# automaton.net
KiCad netlist of a schematic drawn in EAGLE
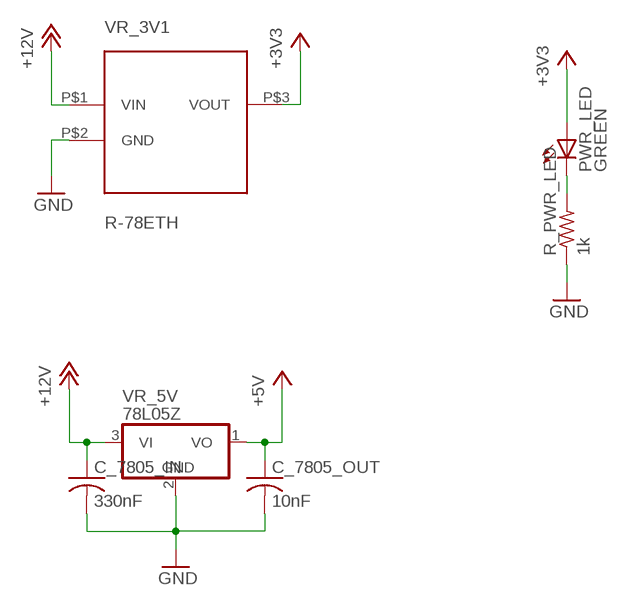
[diagram p0: schematic, sheet 1]
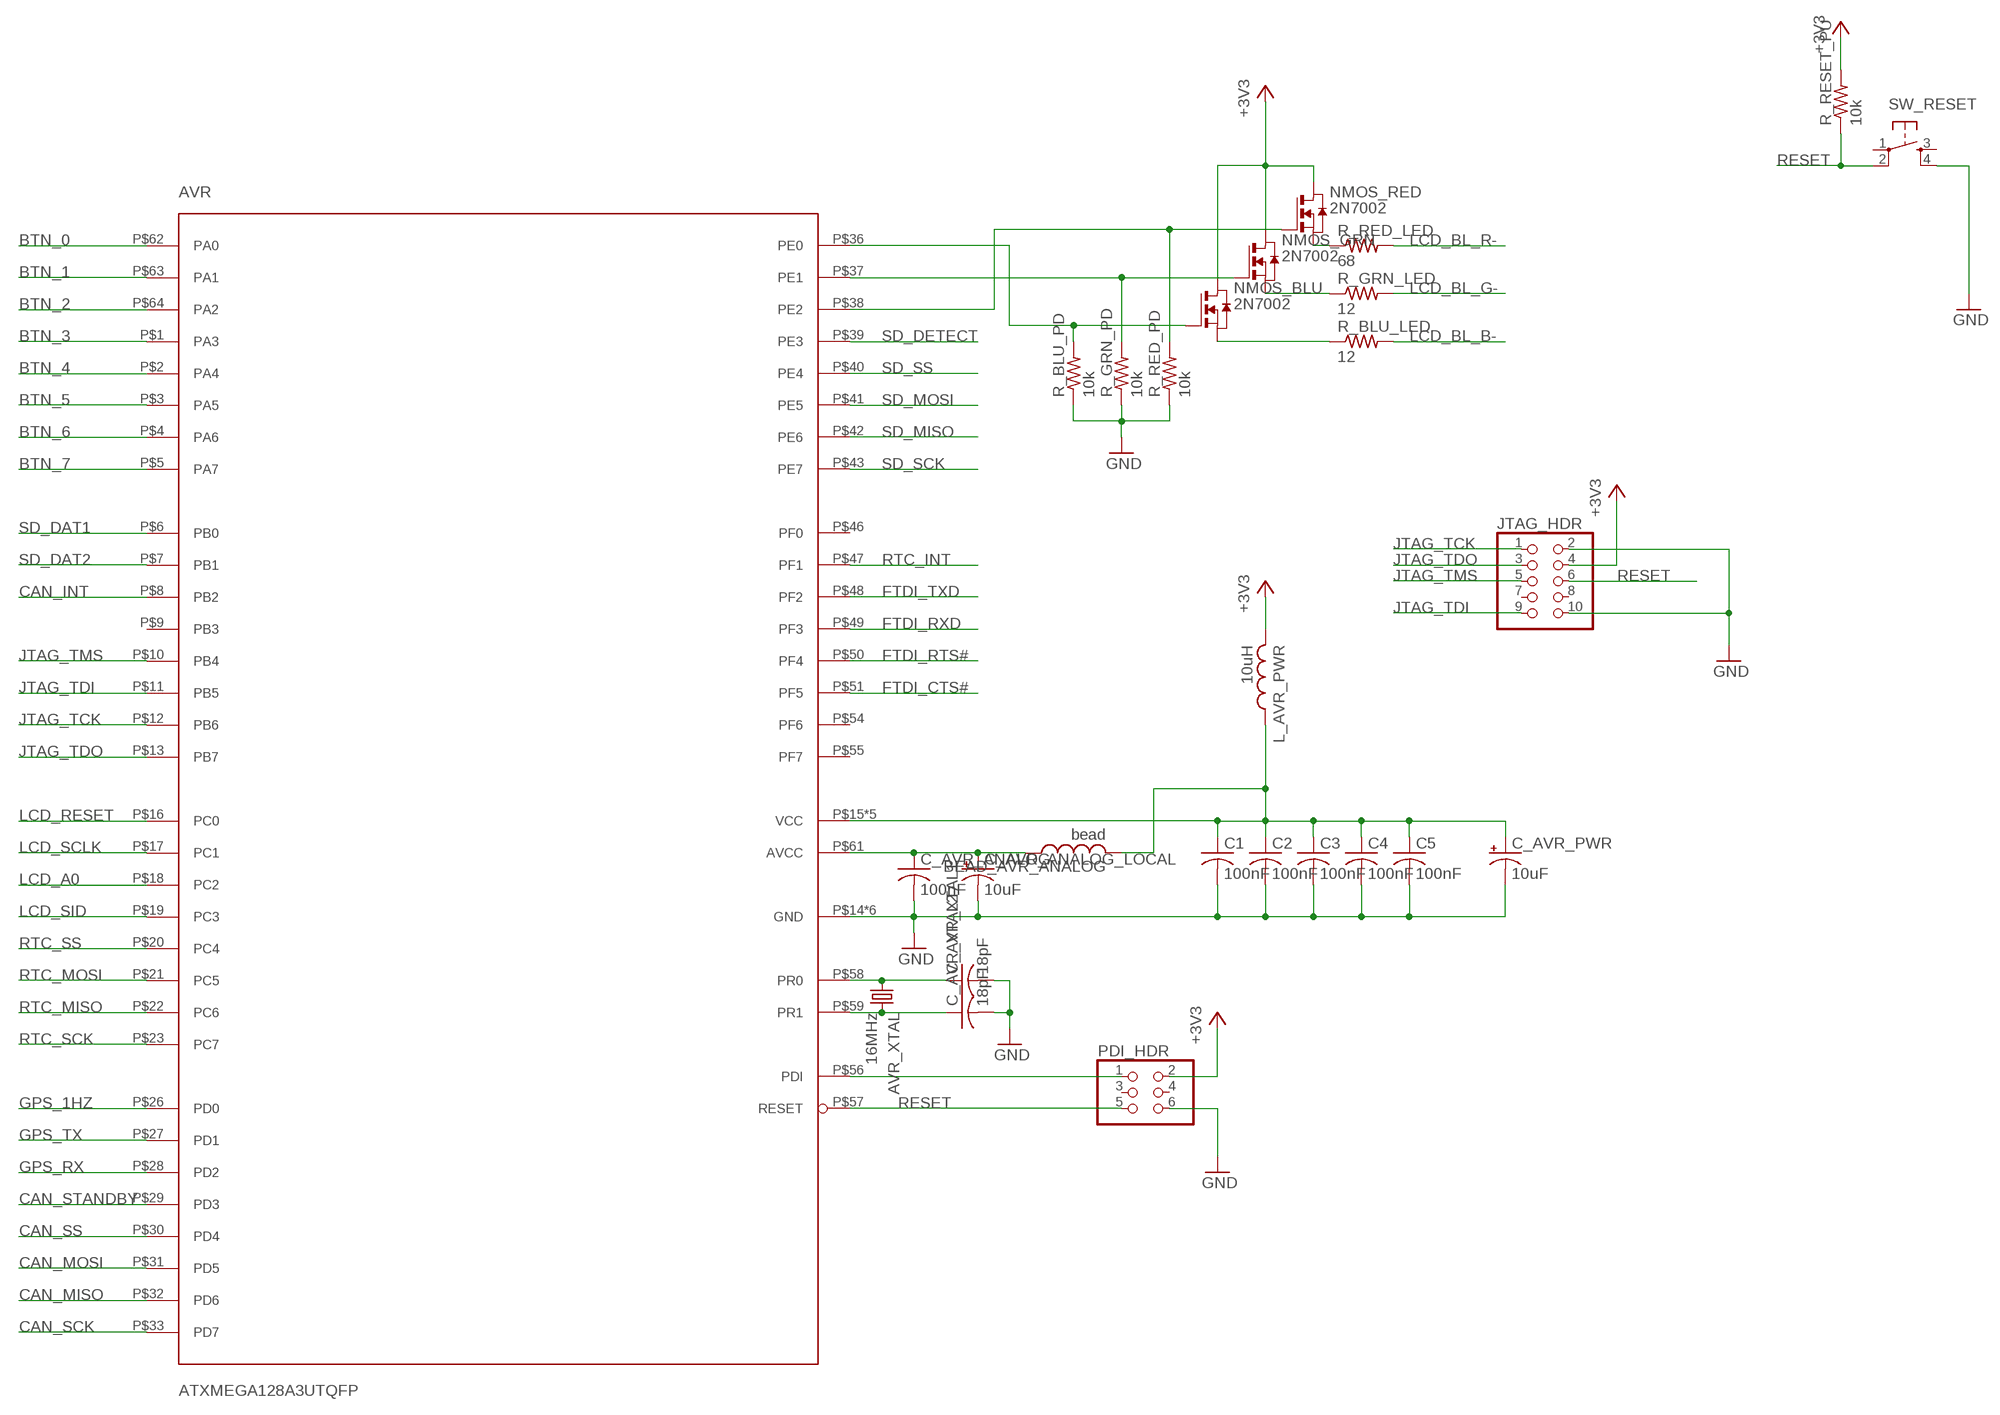
[diagram p1: schematic, sheet 2]
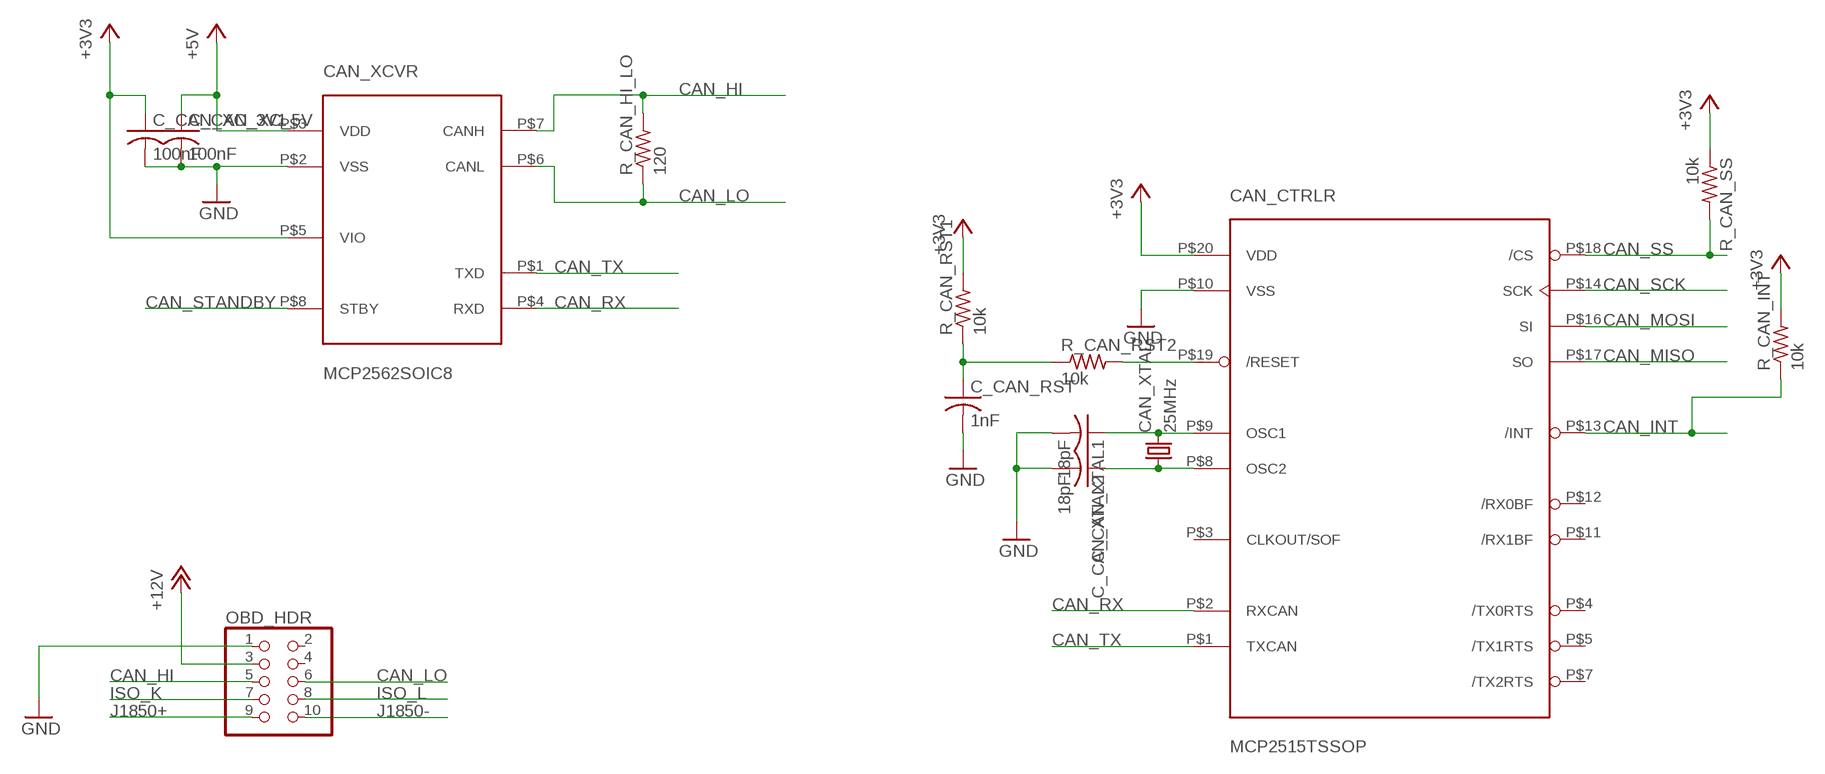
[diagram p2: schematic, sheet 3]
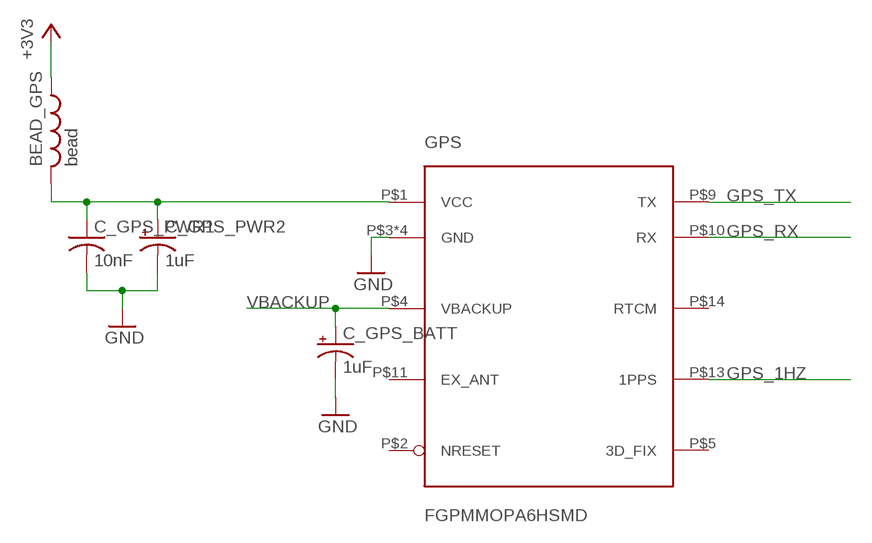
[diagram p3: schematic, sheet 4]
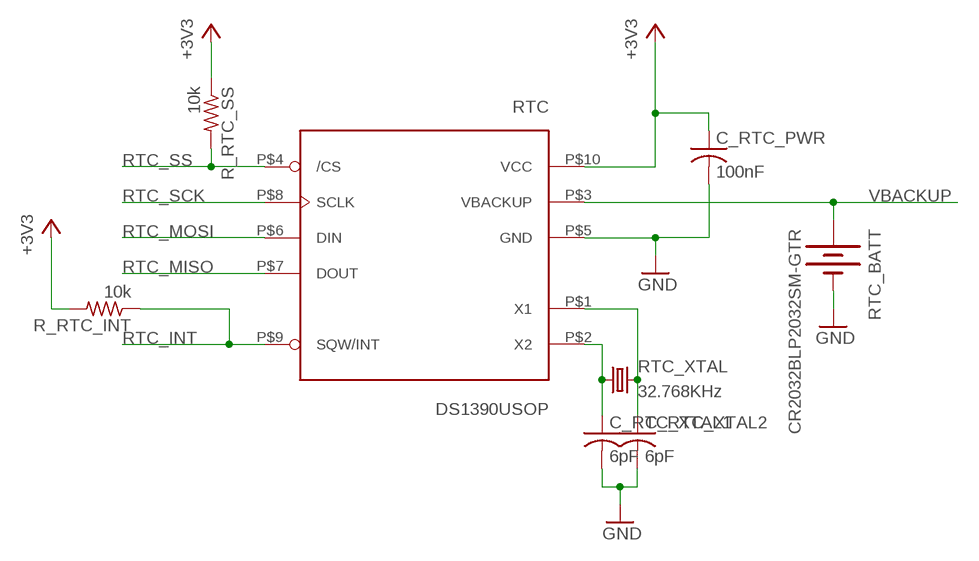
[diagram p4: schematic, sheet 5]
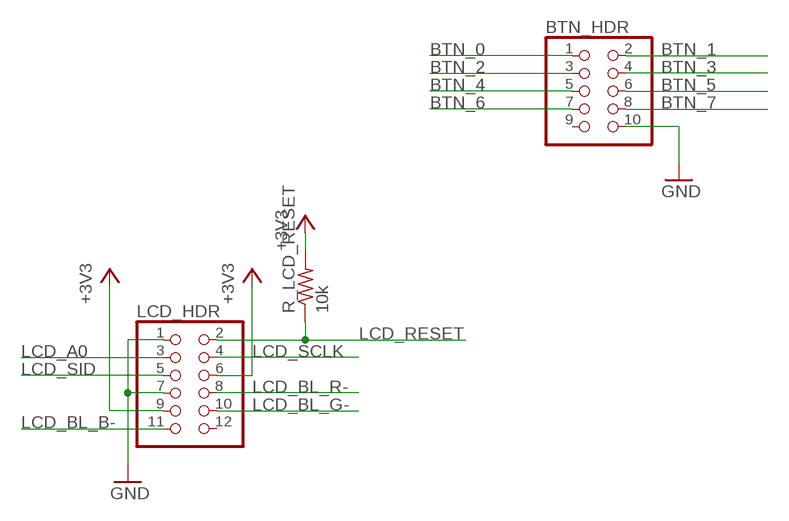
[diagram p5: schematic, sheet 6]
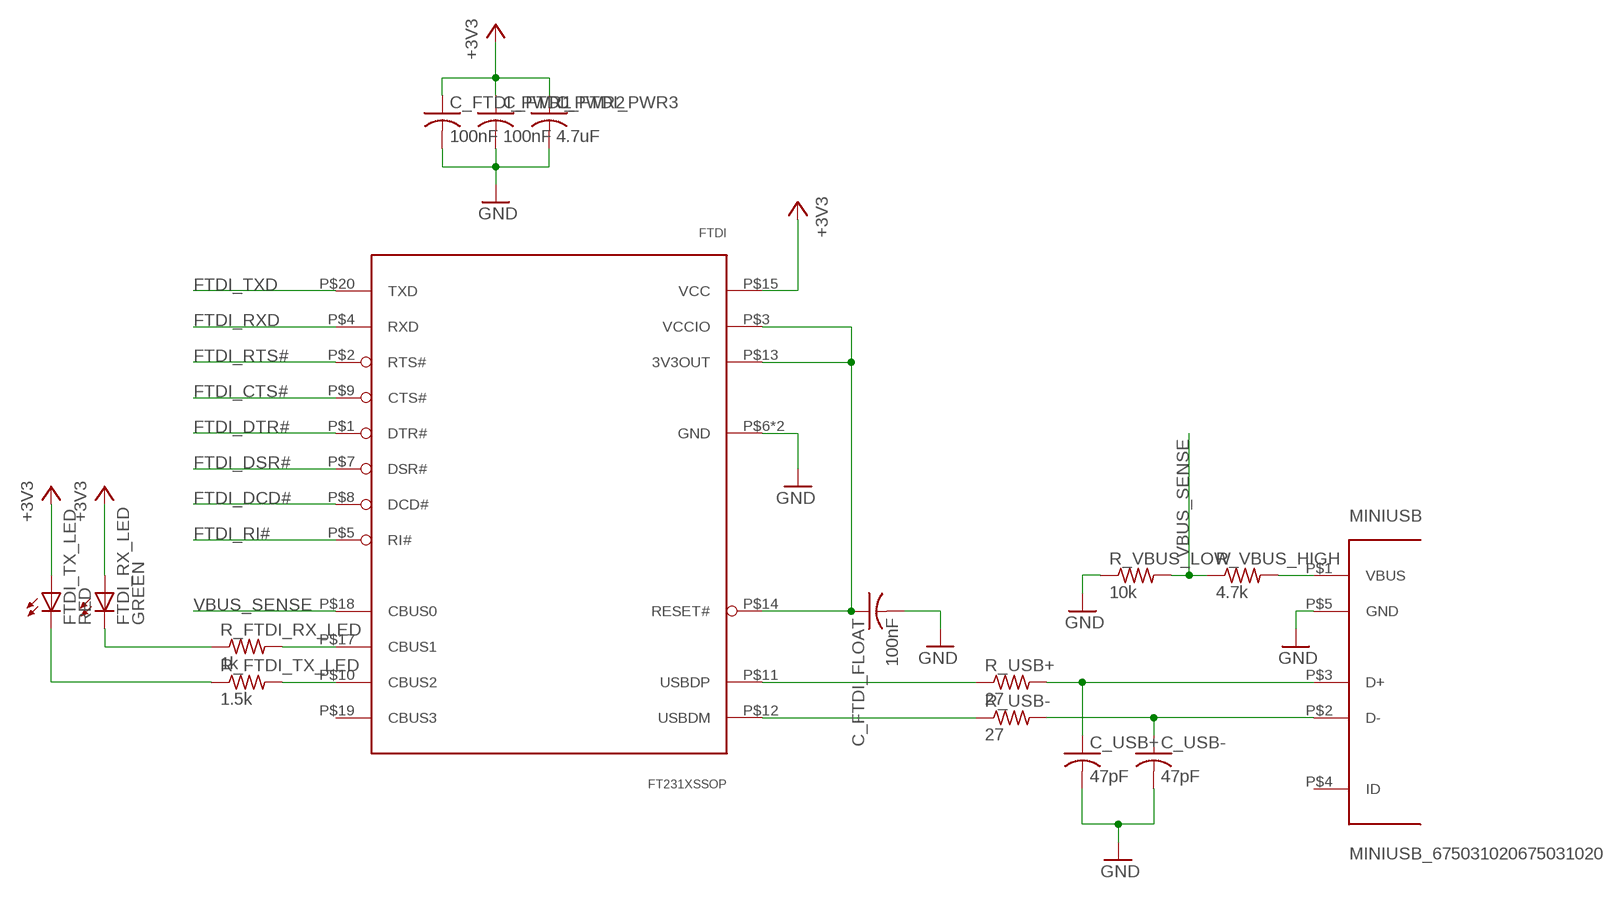
[diagram p6: schematic, sheet 7]
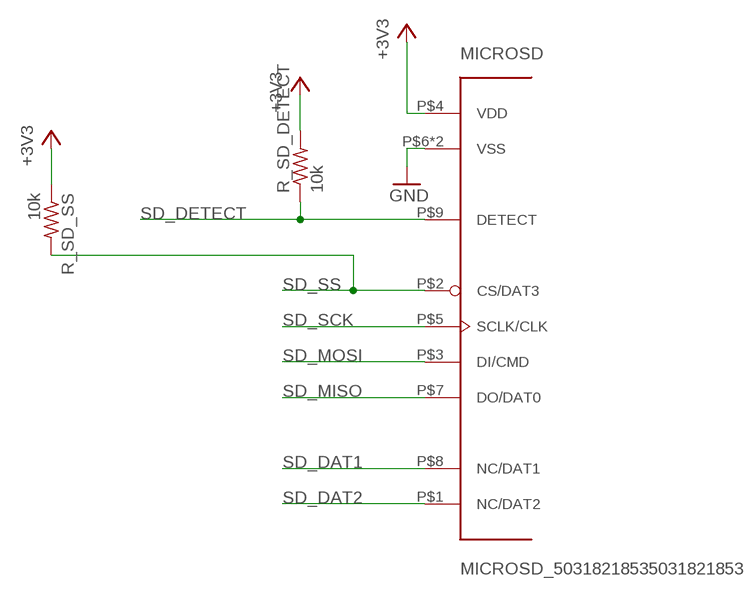
[diagram p7: schematic, sheet 8]

(export (version "E")
  (design (tool "Eeschema 10.0.6"))
  (components
    (comp (ref "C_RTC_PWR")
      (value "100nF")
      (footprint "eagle-import:C1206")
      (libsource (lib "eagle-import") (part "C-USC1206"))
    )
    (comp (ref "C_RTC_XTAL1")
      (value "6pF")
      (footprint "eagle-import:C1206")
      (libsource (lib "eagle-import") (part "C-USC1206"))
    )
    (comp (ref "C_RTC_XTAL2")
      (value "6pF")
      (footprint "eagle-import:C1206")
      (libsource (lib "eagle-import") (part "C-USC1206"))
    )
    (comp (ref "RTC")
      (value "DS1390USOP")
      (footprint "eagle-import:MAXIM_10USOP")
      (libsource (lib "eagle-import") (part "DS1390USOP"))
    )
    (comp (ref "RTC_BATT")
      (value "CR2032BLP2032SM-GTR")
      (footprint "eagle-import:BLP2032SM-GTR")
      (libsource (lib "eagle-import") (part "CR2032BLP2032SM-GTR"))
    )
    (comp (ref "RTC_XTAL")
      (value "32.768KHz")
      (footprint "eagle-import:TC26V")
      (libsource (lib "eagle-import") (part "CRYSTALTC26V"))
    )
    (comp (ref "R_RTC_INT")
      (value "10k")
      (footprint "eagle-import:R1206")
      (libsource (lib "eagle-import") (part "R-US_R1206"))
    )
    (comp (ref "R_RTC_SS")
      (value "10k")
      (footprint "eagle-import:R1206")
      (libsource (lib "eagle-import") (part "R-US_R1206"))
    )
    (comp (ref "BTN_HDR")
      (value "PINHD-2X05_2.54")
      (footprint "eagle-import:2X05")
      (libsource (lib "eagle-import") (part "PINHD-2X05_2.54"))
    )
    (comp (ref "LCD_HDR")
      (value "PINHD-2X06_2.54")
      (footprint "eagle-import:2X06")
      (libsource (lib "eagle-import") (part "PINHD-2X06_2.54"))
    )
    (comp (ref "R_LCD_RESET")
      (value "10k")
      (footprint "eagle-import:R1206")
      (libsource (lib "eagle-import") (part "R-US_R1206"))
    )
    (comp (ref "C_FTDI_FLOAT")
      (value "100nF")
      (footprint "eagle-import:C1206")
      (libsource (lib "eagle-import") (part "C-USC1206"))
    )
    (comp (ref "C_FTDI_PWR1")
      (value "100nF")
      (footprint "eagle-import:C1206")
      (libsource (lib "eagle-import") (part "C-USC1206"))
    )
    (comp (ref "C_FTDI_PWR2")
      (value "100nF")
      (footprint "eagle-import:C1206")
      (libsource (lib "eagle-import") (part "C-USC1206"))
    )
    (comp (ref "C_FTDI_PWR3")
      (value "4.7uF")
      (footprint "eagle-import:C1206")
      (libsource (lib "eagle-import") (part "C-USC1206"))
    )
    (comp (ref "C_USB+")
      (value "47pF")
      (footprint "eagle-import:C1206")
      (libsource (lib "eagle-import") (part "C-USC1206"))
    )
    (comp (ref "C_USB-")
      (value "47pF")
      (footprint "eagle-import:C1206")
      (libsource (lib "eagle-import") (part "C-USC1206"))
    )
    (comp (ref "FTDI")
      (value "FT231XSSOP")
      (footprint "eagle-import:FTDI_SSOP20")
      (libsource (lib "eagle-import") (part "FT231XSSOP"))
    )
    (comp (ref "FTDI_RX_LED")
      (value "GREEN")
      (footprint "eagle-import:CHIPLED_1206")
      (libsource (lib "eagle-import") (part "LEDCHIPLED_1206"))
    )
    (comp (ref "FTDI_TX_LED")
      (value "RED")
      (footprint "eagle-import:CHIPLED_1206")
      (libsource (lib "eagle-import") (part "LEDCHIPLED_1206"))
    )
    (comp (ref "MINIUSB")
      (value "MINIUSB_675031020675031020")
      (footprint "eagle-import:MINIUSB_675031020")
      (libsource (lib "eagle-import") (part "MINIUSB_675031020675031020"))
    )
    (comp (ref "R_FTDI_RX_LED")
      (value "1k")
      (footprint "eagle-import:R1206")
      (libsource (lib "eagle-import") (part "R-US_R1206"))
    )
    (comp (ref "R_FTDI_TX_LED")
      (value "1.5k")
      (footprint "eagle-import:R1206")
      (libsource (lib "eagle-import") (part "R-US_R1206"))
    )
    (comp (ref "R_USB+")
      (value "27")
      (footprint "eagle-import:R1206")
      (libsource (lib "eagle-import") (part "R-US_R1206"))
    )
    (comp (ref "R_USB-")
      (value "27")
      (footprint "eagle-import:R1206")
      (libsource (lib "eagle-import") (part "R-US_R1206"))
    )
    (comp (ref "R_VBUS_HIGH")
      (value "4.7k")
      (footprint "eagle-import:R1206")
      (libsource (lib "eagle-import") (part "R-US_R1206"))
    )
    (comp (ref "R_VBUS_LOW")
      (value "10k")
      (footprint "eagle-import:R1206")
      (libsource (lib "eagle-import") (part "R-US_R1206"))
    )
    (comp (ref "C_7805_IN")
      (value "330nF")
      (footprint "eagle-import:C1206")
      (libsource (lib "eagle-import") (part "C-USC1206"))
    )
    (comp (ref "C_7805_OUT")
      (value "10nF")
      (footprint "eagle-import:C1206")
      (libsource (lib "eagle-import") (part "C-USC1206"))
    )
    (comp (ref "PWR_LED")
      (value "GREEN")
      (footprint "eagle-import:CHIPLED_1206")
      (libsource (lib "eagle-import") (part "LEDCHIPLED_1206"))
    )
    (comp (ref "R_PWR_LED")
      (value "1k")
      (footprint "eagle-import:R1206")
      (libsource (lib "eagle-import") (part "R-US_R1206"))
    )
    (comp (ref "VR_3V1")
      (value "R-78ETH")
      (footprint "eagle-import:R-78E")
      (libsource (lib "eagle-import") (part "R-78ETH"))
    )
    (comp (ref "VR_5V")
      (value "78L05Z")
      (footprint "eagle-import:TO92")
      (libsource (lib "eagle-import") (part "78ZL05"))
    )
    (comp (ref "MICROSD")
      (value "MICROSD_50318218535031821853")
      (footprint "eagle-import:MICROSD_5031821853")
      (libsource (lib "eagle-import") (part "MICROSD_50318218535031821853"))
    )
    (comp (ref "R_SD_DETECT")
      (value "10k")
      (footprint "eagle-import:R1206")
      (libsource (lib "eagle-import") (part "R-US_R1206"))
    )
    (comp (ref "R_SD_SS")
      (value "10k")
      (footprint "eagle-import:R1206")
      (libsource (lib "eagle-import") (part "R-US_R1206"))
    )
    (comp (ref "CAN_CTRLR")
      (value "MCP2515TSSOP")
      (footprint "eagle-import:MICROCHIP_TSSOP20")
      (libsource (lib "eagle-import") (part "MCP2515TSSOP"))
    )
    (comp (ref "CAN_XCVR")
      (value "MCP2562SOIC8")
      (footprint "eagle-import:MICROCHIP_SOIC8")
      (libsource (lib "eagle-import") (part "MCP2562SOIC8"))
    )
    (comp (ref "CAN_XTAL")
      (value "25MHz")
      (footprint "eagle-import:HC49_S")
      (libsource (lib "eagle-import") (part "CRYSTALHC49S"))
    )
    (comp (ref "C_CAN_RST")
      (value "1nF")
      (footprint "eagle-import:C1206")
      (libsource (lib "eagle-import") (part "C-USC1206"))
    )
    (comp (ref "C_CAN_XC_3V1")
      (value "100nF")
      (footprint "eagle-import:C1206")
      (libsource (lib "eagle-import") (part "C-USC1206"))
    )
    (comp (ref "C_CAN_XC_5V")
      (value "100nF")
      (footprint "eagle-import:C1206")
      (libsource (lib "eagle-import") (part "C-USC1206"))
    )
    (comp (ref "C_CAN_XTAL1")
      (value "18pF")
      (footprint "eagle-import:C1206")
      (libsource (lib "eagle-import") (part "C-USC1206"))
    )
    (comp (ref "C_CAN_XTAL2")
      (value "18pF")
      (footprint "eagle-import:C1206")
      (libsource (lib "eagle-import") (part "C-USC1206"))
    )
    (comp (ref "OBD_HDR")
      (value "PINHD-2X05_2.54-90°")
      (footprint "eagle-import:2X05_90")
      (libsource (lib "eagle-import") (part "PINHD-2X05_2.54-90°"))
    )
    (comp (ref "R_CAN_HI_LO")
      (value "120")
      (footprint "eagle-import:R1206")
      (libsource (lib "eagle-import") (part "R-US_R1206"))
    )
    (comp (ref "R_CAN_INT")
      (value "10k")
      (footprint "eagle-import:R1206")
      (libsource (lib "eagle-import") (part "R-US_R1206"))
    )
    (comp (ref "R_CAN_RST1")
      (value "10k")
      (footprint "eagle-import:R1206")
      (libsource (lib "eagle-import") (part "R-US_R1206"))
    )
    (comp (ref "R_CAN_RST2")
      (value "10k")
      (footprint "eagle-import:R1206")
      (libsource (lib "eagle-import") (part "R-US_R1206"))
    )
    (comp (ref "R_CAN_SS")
      (value "10k")
      (footprint "eagle-import:R1206")
      (libsource (lib "eagle-import") (part "R-US_R1206"))
    )
    (comp (ref "AVR")
      (value "ATXMEGA128A3UTQFP")
      (footprint "eagle-import:ATMEL_TQFP64")
      (libsource (lib "eagle-import") (part "ATXMEGA128A3UTQFP"))
    )
    (comp (ref "AVR_XTAL")
      (value "16MHz")
      (footprint "eagle-import:HC49_S")
      (libsource (lib "eagle-import") (part "CRYSTALHC49S"))
    )
    (comp (ref "BEAD_AVR_ANALOG")
      (value "bead")
      (footprint "eagle-import:L1812")
      (libsource (lib "eagle-import") (part "L-USL1812"))
    )
    (comp (ref "C1")
      (value "100nF")
      (footprint "eagle-import:C1206")
      (libsource (lib "eagle-import") (part "C-USC1206"))
    )
    (comp (ref "C2")
      (value "100nF")
      (footprint "eagle-import:C1206")
      (libsource (lib "eagle-import") (part "C-USC1206"))
    )
    (comp (ref "C3")
      (value "100nF")
      (footprint "eagle-import:C1206")
      (libsource (lib "eagle-import") (part "C-USC1206"))
    )
    (comp (ref "C4")
      (value "100nF")
      (footprint "eagle-import:C1206")
      (libsource (lib "eagle-import") (part "C-USC1206"))
    )
    (comp (ref "C5")
      (value "100nF")
      (footprint "eagle-import:C1206")
      (libsource (lib "eagle-import") (part "C-USC1206"))
    )
    (comp (ref "C_AVR_ANALOG")
      (value "100nF")
      (footprint "eagle-import:C1206")
      (libsource (lib "eagle-import") (part "C-USC1206"))
    )
    (comp (ref "C_AVR_ANALOG_LOCAL")
      (value "10uF")
      (footprint "eagle-import:E2-5")
      (libsource (lib "eagle-import") (part "CPOL-USE2-5"))
    )
    (comp (ref "C_AVR_PWR")
      (value "10uF")
      (footprint "eagle-import:E2-5")
      (libsource (lib "eagle-import") (part "CPOL-USE2-5"))
    )
    (comp (ref "C_AVR_XTAL1")
      (value "18pF")
      (footprint "eagle-import:C1206")
      (libsource (lib "eagle-import") (part "C-USC1206"))
    )
    (comp (ref "C_AVR_XTAL2")
      (value "18pF")
      (footprint "eagle-import:C1206")
      (libsource (lib "eagle-import") (part "C-USC1206"))
    )
    (comp (ref "JTAG_HDR")
      (value "PINHD-2X05_2.54")
      (footprint "eagle-import:2X05")
      (libsource (lib "eagle-import") (part "PINHD-2X05_2.54"))
    )
    (comp (ref "L_AVR_PWR")
      (value "10uH")
      (footprint "eagle-import:L1812")
      (libsource (lib "eagle-import") (part "L-USL1812"))
    )
    (comp (ref "NMOS_BLU")
      (value "2N7002")
      (footprint "eagle-import:SOT-23")
      (libsource (lib "eagle-import") (part "NMOSSOT23"))
    )
    (comp (ref "NMOS_GRN")
      (value "2N7002")
      (footprint "eagle-import:SOT-23")
      (libsource (lib "eagle-import") (part "NMOSSOT23"))
    )
    (comp (ref "NMOS_RED")
      (value "2N7002")
      (footprint "eagle-import:SOT-23")
      (libsource (lib "eagle-import") (part "NMOSSOT23"))
    )
    (comp (ref "PDI_HDR")
      (value "PINHD-2X03_2.54")
      (footprint "eagle-import:2X03")
      (libsource (lib "eagle-import") (part "PINHD-2X03_2.54"))
    )
    (comp (ref "R_BLU_LED")
      (value "12")
      (footprint "eagle-import:R1206")
      (libsource (lib "eagle-import") (part "R-US_R1206"))
    )
    (comp (ref "R_BLU_PD")
      (value "10k")
      (footprint "eagle-import:R1206")
      (libsource (lib "eagle-import") (part "R-US_R1206"))
    )
    (comp (ref "R_GRN_LED")
      (value "12")
      (footprint "eagle-import:R1206")
      (libsource (lib "eagle-import") (part "R-US_R1206"))
    )
    (comp (ref "R_GRN_PD")
      (value "10k")
      (footprint "eagle-import:R1206")
      (libsource (lib "eagle-import") (part "R-US_R1206"))
    )
    (comp (ref "R_RED_LED")
      (value "68")
      (footprint "eagle-import:R1206")
      (libsource (lib "eagle-import") (part "R-US_R1206"))
    )
    (comp (ref "R_RED_PD")
      (value "10k")
      (footprint "eagle-import:R1206")
      (libsource (lib "eagle-import") (part "R-US_R1206"))
    )
    (comp (ref "R_RESET_PU")
      (value "10k")
      (footprint "eagle-import:R1206")
      (libsource (lib "eagle-import") (part "R-US_R1206"))
    )
    (comp (ref "SW_RESET")
      (value "TAC_SWITCHSMD")
      (footprint "eagle-import:TACTILE_SWITCH_SMD")
      (libsource (lib "eagle-import") (part "TAC_SWITCHSMD"))
    )
    (comp (ref "BEAD_GPS")
      (value "bead")
      (footprint "eagle-import:L1812")
      (libsource (lib "eagle-import") (part "L-USL1812"))
    )
    (comp (ref "C_GPS_BATT")
      (value "1uF")
      (footprint "eagle-import:E2-5")
      (libsource (lib "eagle-import") (part "CPOL-USE2-5"))
    )
    (comp (ref "C_GPS_PWR1")
      (value "10nF")
      (footprint "eagle-import:C1206")
      (libsource (lib "eagle-import") (part "C-USC1206"))
    )
    (comp (ref "C_GPS_PWR2")
      (value "1uF")
      (footprint "eagle-import:E2-5")
      (libsource (lib "eagle-import") (part "CPOL-USE2-5"))
    )
    (comp (ref "GPS")
      (value "FGPMMOPA6HSMD")
      (footprint "eagle-import:FGPMMOPA6H")
      (libsource (lib "eagle-import") (part "FGPMMOPA6HSMD"))
    )
  )
  (nets
    (net (code "1") (name "+3V3") (class "Default")
      (node (ref "BEAD_GPS") (pin "1") (pinfunction "1_1") (pintype "passive"))
      (node (ref "CAN_CTRLR") (pin "P$20") (pinfunction "VDD_P$20") (pintype "power_in"))
      (node (ref "CAN_XCVR") (pin "P$5") (pinfunction "VIO_P$5") (pintype "power_in"))
      (node (ref "C_CAN_XC_3V1") (pin "1") (pinfunction "1_1") (pintype "passive"))
      (node (ref "C_FTDI_PWR1") (pin "1") (pinfunction "1_1") (pintype "passive"))
      (node (ref "C_FTDI_PWR2") (pin "1") (pinfunction "1_1") (pintype "passive"))
      (node (ref "C_FTDI_PWR3") (pin "1") (pinfunction "1_1") (pintype "passive"))
      (node (ref "C_RTC_PWR") (pin "1") (pinfunction "1_1") (pintype "passive"))
      (node (ref "FTDI") (pin "P$15") (pinfunction "VCC_P$15") (pintype "power_in"))
      (node (ref "FTDI_RX_LED") (pin "A") (pinfunction "A_A") (pintype "passive"))
      (node (ref "FTDI_TX_LED") (pin "A") (pinfunction "A_A") (pintype "passive"))
      (node (ref "JTAG_HDR") (pin "4") (pinfunction "4_4") (pintype "passive"))
      (node (ref "LCD_HDR") (pin "6") (pinfunction "6_6") (pintype "passive"))
      (node (ref "LCD_HDR") (pin "9") (pinfunction "9_9") (pintype "passive"))
      (node (ref "L_AVR_PWR") (pin "2") (pinfunction "2_2") (pintype "passive"))
      (node (ref "MICROSD") (pin "P$4") (pinfunction "VDD_P$4") (pintype "power_in"))
      (node (ref "NMOS_BLU") (pin "1") (pinfunction "D_1") (pintype "passive"))
      (node (ref "NMOS_GRN") (pin "1") (pinfunction "D_1") (pintype "passive"))
      (node (ref "NMOS_RED") (pin "1") (pinfunction "D_1") (pintype "passive"))
      (node (ref "PDI_HDR") (pin "2") (pinfunction "2_2") (pintype "passive"))
      (node (ref "PWR_LED") (pin "A") (pinfunction "A_A") (pintype "passive"))
      (node (ref "RTC") (pin "P$10") (pinfunction "VCC_P$10") (pintype "power_in"))
      (node (ref "R_CAN_INT") (pin "2") (pinfunction "2_2") (pintype "passive"))
      (node (ref "R_CAN_RST1") (pin "2") (pinfunction "2_2") (pintype "passive"))
      (node (ref "R_CAN_SS") (pin "1") (pinfunction "1_1") (pintype "passive"))
      (node (ref "R_LCD_RESET") (pin "2") (pinfunction "2_2") (pintype "passive"))
      (node (ref "R_RESET_PU") (pin "2") (pinfunction "2_2") (pintype "passive"))
      (node (ref "R_RTC_INT") (pin "2") (pinfunction "2_2") (pintype "passive"))
      (node (ref "R_RTC_SS") (pin "1") (pinfunction "1_1") (pintype "passive"))
      (node (ref "R_SD_DETECT") (pin "2") (pinfunction "2_2") (pintype "passive"))
      (node (ref "R_SD_SS") (pin "1") (pinfunction "1_1") (pintype "passive"))
      (node (ref "VR_3V1") (pin "P$3") (pinfunction "VOUT_P$3") (pintype "power_in"))
    )
    (net (code "2") (name "+5V") (class "Default")
      (node (ref "CAN_XCVR") (pin "P$3") (pinfunction "VDD_P$3") (pintype "power_in"))
      (node (ref "C_7805_OUT") (pin "1") (pinfunction "1_1") (pintype "passive"))
      (node (ref "C_CAN_XC_5V") (pin "1") (pinfunction "1_1") (pintype "passive"))
      (node (ref "VR_5V") (pin "1") (pinfunction "VO_1") (pintype "passive"))
    )
    (net (code "3") (name "+12V") (class "Default")
      (node (ref "C_7805_IN") (pin "1") (pinfunction "1_1") (pintype "passive"))
      (node (ref "OBD_HDR") (pin "3") (pinfunction "3_3") (pintype "passive"))
      (node (ref "VR_3V1") (pin "P$1") (pinfunction "VIN_P$1") (pintype "power_in"))
      (node (ref "VR_5V") (pin "3") (pinfunction "VI_3") (pintype "input"))
    )
    (net (code "4") (name "BTN_0") (class "Default")
      (node (ref "AVR") (pin "P$62") (pinfunction "PA0_P$62") (pintype "bidirectional"))
      (node (ref "BTN_HDR") (pin "1") (pinfunction "1_1") (pintype "passive"))
    )
    (net (code "5") (name "BTN_1") (class "Default")
      (node (ref "AVR") (pin "P$63") (pinfunction "PA1_P$63") (pintype "bidirectional"))
      (node (ref "BTN_HDR") (pin "2") (pinfunction "2_2") (pintype "passive"))
    )
    (net (code "6") (name "BTN_2") (class "Default")
      (node (ref "AVR") (pin "P$64") (pinfunction "PA2_P$64") (pintype "bidirectional"))
      (node (ref "BTN_HDR") (pin "3") (pinfunction "3_3") (pintype "passive"))
    )
    (net (code "7") (name "BTN_3") (class "Default")
      (node (ref "AVR") (pin "P$1") (pinfunction "PA3_P$1") (pintype "bidirectional"))
      (node (ref "BTN_HDR") (pin "4") (pinfunction "4_4") (pintype "passive"))
    )
    (net (code "8") (name "BTN_4") (class "Default")
      (node (ref "AVR") (pin "P$2") (pinfunction "PA4_P$2") (pintype "bidirectional"))
      (node (ref "BTN_HDR") (pin "5") (pinfunction "5_5") (pintype "passive"))
    )
    (net (code "9") (name "BTN_5") (class "Default")
      (node (ref "AVR") (pin "P$3") (pinfunction "PA5_P$3") (pintype "bidirectional"))
      (node (ref "BTN_HDR") (pin "6") (pinfunction "6_6") (pintype "passive"))
    )
    (net (code "10") (name "BTN_6") (class "Default")
      (node (ref "AVR") (pin "P$4") (pinfunction "PA6_P$4") (pintype "bidirectional"))
      (node (ref "BTN_HDR") (pin "7") (pinfunction "7_7") (pintype "passive"))
    )
    (net (code "11") (name "BTN_7") (class "Default")
      (node (ref "AVR") (pin "P$5") (pinfunction "PA7_P$5") (pintype "bidirectional"))
      (node (ref "BTN_HDR") (pin "8") (pinfunction "8_8") (pintype "passive"))
    )
    (net (code "12") (name "CAN_HI") (class "Default")
      (node (ref "CAN_XCVR") (pin "P$7") (pinfunction "CANH_P$7") (pintype "bidirectional"))
      (node (ref "OBD_HDR") (pin "5") (pinfunction "5_5") (pintype "passive"))
      (node (ref "R_CAN_HI_LO") (pin "2") (pinfunction "2_2") (pintype "passive"))
    )
    (net (code "13") (name "CAN_INT") (class "Default")
      (node (ref "AVR") (pin "P$8") (pinfunction "PB2_P$8") (pintype "bidirectional"))
      (node (ref "CAN_CTRLR") (pin "P$13") (pinfunction "/INT_P$13") (pintype "bidirectional"))
      (node (ref "R_CAN_INT") (pin "1") (pinfunction "1_1") (pintype "passive"))
    )
    (net (code "14") (name "CAN_LO") (class "Default")
      (node (ref "CAN_XCVR") (pin "P$6") (pinfunction "CANL_P$6") (pintype "bidirectional"))
      (node (ref "OBD_HDR") (pin "6") (pinfunction "6_6") (pintype "passive"))
      (node (ref "R_CAN_HI_LO") (pin "1") (pinfunction "1_1") (pintype "passive"))
    )
    (net (code "15") (name "CAN_MISO") (class "Default")
      (node (ref "AVR") (pin "P$32") (pinfunction "PD6_P$32") (pintype "bidirectional"))
      (node (ref "CAN_CTRLR") (pin "P$17") (pinfunction "SO_P$17") (pintype "output"))
    )
    (net (code "16") (name "CAN_MOSI") (class "Default")
      (node (ref "AVR") (pin "P$31") (pinfunction "PD5_P$31") (pintype "bidirectional"))
      (node (ref "CAN_CTRLR") (pin "P$16") (pinfunction "SI_P$16") (pintype "input"))
    )
    (net (code "17") (name "CAN_RX") (class "Default")
      (node (ref "CAN_CTRLR") (pin "P$2") (pinfunction "RXCAN_P$2") (pintype "input"))
      (node (ref "CAN_XCVR") (pin "P$4") (pinfunction "RXD_P$4") (pintype "output"))
    )
    (net (code "18") (name "CAN_SCK") (class "Default")
      (node (ref "AVR") (pin "P$33") (pinfunction "PD7_P$33") (pintype "bidirectional"))
      (node (ref "CAN_CTRLR") (pin "P$14") (pinfunction "SCK_P$14") (pintype "input"))
    )
    (net (code "19") (name "CAN_SS") (class "Default")
      (node (ref "AVR") (pin "P$30") (pinfunction "PD4_P$30") (pintype "bidirectional"))
      (node (ref "CAN_CTRLR") (pin "P$18") (pinfunction "/CS_P$18") (pintype "input"))
      (node (ref "R_CAN_SS") (pin "2") (pinfunction "2_2") (pintype "passive"))
    )
    (net (code "20") (name "CAN_STANDBY") (class "Default")
      (node (ref "AVR") (pin "P$29") (pinfunction "PD3_P$29") (pintype "bidirectional"))
      (node (ref "CAN_XCVR") (pin "P$8") (pinfunction "STBY_P$8") (pintype "bidirectional"))
    )
    (net (code "21") (name "CAN_TX") (class "Default")
      (node (ref "CAN_CTRLR") (pin "P$1") (pinfunction "TXCAN_P$1") (pintype "output"))
      (node (ref "CAN_XCVR") (pin "P$1") (pinfunction "TXD_P$1") (pintype "input"))
    )
    (net (code "22") (name "FTDI_CTS#") (class "Default")
      (node (ref "AVR") (pin "P$51") (pinfunction "PF5_P$51") (pintype "bidirectional"))
      (node (ref "FTDI") (pin "P$9") (pinfunction "CTS#_P$9") (pintype "bidirectional"))
    )
    (net (code "23") (name "FTDI_DCD#") (class "Default")
      (node (ref "FTDI") (pin "P$8") (pinfunction "DCD#_P$8") (pintype "bidirectional"))
    )
    (net (code "24") (name "FTDI_DSR#") (class "Default")
      (node (ref "FTDI") (pin "P$7") (pinfunction "DSR#_P$7") (pintype "bidirectional"))
    )
    (net (code "25") (name "FTDI_DTR#") (class "Default")
      (node (ref "FTDI") (pin "P$1") (pinfunction "DTR#_P$1") (pintype "bidirectional"))
    )
    (net (code "26") (name "FTDI_RI#") (class "Default")
      (node (ref "FTDI") (pin "P$5") (pinfunction "RI#_P$5") (pintype "bidirectional"))
    )
    (net (code "27") (name "FTDI_RTS#") (class "Default")
      (node (ref "AVR") (pin "P$50") (pinfunction "PF4_P$50") (pintype "bidirectional"))
      (node (ref "FTDI") (pin "P$2") (pinfunction "RTS#_P$2") (pintype "bidirectional"))
    )
    (net (code "28") (name "FTDI_RXD") (class "Default")
      (node (ref "AVR") (pin "P$49") (pinfunction "PF3_P$49") (pintype "bidirectional"))
      (node (ref "FTDI") (pin "P$4") (pinfunction "RXD_P$4") (pintype "input"))
    )
    (net (code "29") (name "FTDI_TXD") (class "Default")
      (node (ref "AVR") (pin "P$48") (pinfunction "PF2_P$48") (pintype "bidirectional"))
      (node (ref "FTDI") (pin "P$20") (pinfunction "TXD_P$20") (pintype "output"))
    )
    (net (code "30") (name "GND") (class "Default")
      (node (ref "AVR") (pin "P$14") (pinfunction "GND_P$14") (pintype "power_in"))
      (node (ref "AVR") (pin "P$24") (pinfunction "GND_P$24") (pintype "power_in"))
      (node (ref "AVR") (pin "P$34") (pinfunction "GND_P$34") (pintype "power_in"))
      (node (ref "AVR") (pin "P$44") (pinfunction "GND_P$44") (pintype "power_in"))
      (node (ref "AVR") (pin "P$52") (pinfunction "GND_P$52") (pintype "power_in"))
      (node (ref "AVR") (pin "P$60") (pinfunction "GND_P$60") (pintype "power_in"))
      (node (ref "BTN_HDR") (pin "10") (pinfunction "10_10") (pintype "passive"))
      (node (ref "C1") (pin "2") (pinfunction "2_2") (pintype "passive"))
      (node (ref "C2") (pin "2") (pinfunction "2_2") (pintype "passive"))
      (node (ref "C3") (pin "2") (pinfunction "2_2") (pintype "passive"))
      (node (ref "C4") (pin "2") (pinfunction "2_2") (pintype "passive"))
      (node (ref "C5") (pin "2") (pinfunction "2_2") (pintype "passive"))
      (node (ref "CAN_CTRLR") (pin "P$10") (pinfunction "VSS_P$10") (pintype "power_in"))
      (node (ref "CAN_XCVR") (pin "P$2") (pinfunction "VSS_P$2") (pintype "power_in"))
      (node (ref "C_7805_IN") (pin "2") (pinfunction "2_2") (pintype "passive"))
      (node (ref "C_7805_OUT") (pin "2") (pinfunction "2_2") (pintype "passive"))
      (node (ref "C_AVR_ANALOG") (pin "2") (pinfunction "2_2") (pintype "passive"))
      (node (ref "C_AVR_ANALOG_LOCAL") (pin "-") (pinfunction "-_-") (pintype "passive"))
      (node (ref "C_AVR_PWR") (pin "-") (pinfunction "-_-") (pintype "passive"))
      (node (ref "C_AVR_XTAL1") (pin "2") (pinfunction "2_2") (pintype "passive"))
      (node (ref "C_AVR_XTAL2") (pin "2") (pinfunction "2_2") (pintype "passive"))
      (node (ref "C_CAN_RST") (pin "2") (pinfunction "2_2") (pintype "passive"))
      (node (ref "C_CAN_XC_3V1") (pin "2") (pinfunction "2_2") (pintype "passive"))
      (node (ref "C_CAN_XC_5V") (pin "2") (pinfunction "2_2") (pintype "passive"))
      (node (ref "C_CAN_XTAL1") (pin "2") (pinfunction "2_2") (pintype "passive"))
      (node (ref "C_CAN_XTAL2") (pin "2") (pinfunction "2_2") (pintype "passive"))
      (node (ref "C_FTDI_FLOAT") (pin "2") (pinfunction "2_2") (pintype "passive"))
      (node (ref "C_FTDI_PWR1") (pin "2") (pinfunction "2_2") (pintype "passive"))
      (node (ref "C_FTDI_PWR2") (pin "2") (pinfunction "2_2") (pintype "passive"))
      (node (ref "C_FTDI_PWR3") (pin "2") (pinfunction "2_2") (pintype "passive"))
      (node (ref "C_GPS_BATT") (pin "-") (pinfunction "-_-") (pintype "passive"))
      (node (ref "C_GPS_PWR1") (pin "2") (pinfunction "2_2") (pintype "passive"))
      (node (ref "C_GPS_PWR2") (pin "-") (pinfunction "-_-") (pintype "passive"))
      (node (ref "C_RTC_PWR") (pin "2") (pinfunction "2_2") (pintype "passive"))
      (node (ref "C_RTC_XTAL1") (pin "2") (pinfunction "2_2") (pintype "passive"))
      (node (ref "C_RTC_XTAL2") (pin "2") (pinfunction "2_2") (pintype "passive"))
      (node (ref "C_USB+") (pin "2") (pinfunction "2_2") (pintype "passive"))
      (node (ref "C_USB-") (pin "2") (pinfunction "2_2") (pintype "passive"))
      (node (ref "FTDI") (pin "P$16") (pinfunction "GND_P$16") (pintype "power_in"))
      (node (ref "FTDI") (pin "P$6") (pinfunction "GND_P$6") (pintype "power_in"))
      (node (ref "GPS") (pin "P$12") (pinfunction "GND_P$12") (pintype "power_in"))
      (node (ref "GPS") (pin "P$19") (pinfunction "GND_P$19") (pintype "power_in"))
      (node (ref "GPS") (pin "P$3") (pinfunction "GND_P$3") (pintype "power_in"))
      (node (ref "GPS") (pin "P$8") (pinfunction "GND_P$8") (pintype "power_in"))
      (node (ref "JTAG_HDR") (pin "10") (pinfunction "10_10") (pintype "passive"))
      (node (ref "JTAG_HDR") (pin "2") (pinfunction "2_2") (pintype "passive"))
      (node (ref "LCD_HDR") (pin "1") (pinfunction "1_1") (pintype "passive"))
      (node (ref "LCD_HDR") (pin "7") (pinfunction "7_7") (pintype "passive"))
      (node (ref "MICROSD") (pin "P$10") (pinfunction "VSS_P$10") (pintype "power_in"))
      (node (ref "MICROSD") (pin "P$6") (pinfunction "VSS_P$6") (pintype "power_in"))
      (node (ref "MINIUSB") (pin "P$5") (pinfunction "GND_P$5") (pintype "power_in"))
      (node (ref "OBD_HDR") (pin "1") (pinfunction "1_1") (pintype "passive"))
      (node (ref "PDI_HDR") (pin "6") (pinfunction "6_6") (pintype "passive"))
      (node (ref "RTC") (pin "P$5") (pinfunction "GND_P$5") (pintype "power_in"))
      (node (ref "RTC_BATT") (pin "P$2") (pinfunction "-_P$2") (pintype "power_in"))
      (node (ref "R_BLU_PD") (pin "1") (pinfunction "1_1") (pintype "passive"))
      (node (ref "R_GRN_PD") (pin "1") (pinfunction "1_1") (pintype "passive"))
      (node (ref "R_PWR_LED") (pin "1") (pinfunction "1_1") (pintype "passive"))
      (node (ref "R_RED_PD") (pin "1") (pinfunction "1_1") (pintype "passive"))
      (node (ref "R_VBUS_LOW") (pin "1") (pinfunction "1_1") (pintype "passive"))
      (node (ref "SW_RESET") (pin "4") (pinfunction "4_4") (pintype "passive"))
      (node (ref "VR_3V1") (pin "P$2") (pinfunction "GND_P$2") (pintype "power_in"))
      (node (ref "VR_5V") (pin "2") (pinfunction "GND_2") (pintype "passive"))
    )
    (net (code "31") (name "GPS_1HZ") (class "Default")
      (node (ref "AVR") (pin "P$26") (pinfunction "PD0_P$26") (pintype "bidirectional"))
      (node (ref "GPS") (pin "P$13") (pinfunction "1PPS_P$13") (pintype "bidirectional"))
    )
    (net (code "32") (name "GPS_RX") (class "Default")
      (node (ref "AVR") (pin "P$28") (pinfunction "PD2_P$28") (pintype "bidirectional"))
      (node (ref "GPS") (pin "P$10") (pinfunction "RX_P$10") (pintype "input"))
    )
    (net (code "33") (name "GPS_TX") (class "Default")
      (node (ref "AVR") (pin "P$27") (pinfunction "PD1_P$27") (pintype "bidirectional"))
      (node (ref "GPS") (pin "P$9") (pinfunction "TX_P$9") (pintype "output"))
    )
    (net (code "34") (name "ISO_K") (class "Default")
      (node (ref "OBD_HDR") (pin "7") (pinfunction "7_7") (pintype "passive"))
    )
    (net (code "35") (name "ISO_L") (class "Default")
      (node (ref "OBD_HDR") (pin "8") (pinfunction "8_8") (pintype "passive"))
    )
    (net (code "36") (name "J1850+") (class "Default")
      (node (ref "OBD_HDR") (pin "9") (pinfunction "9_9") (pintype "passive"))
    )
    (net (code "37") (name "J1850-") (class "Default")
      (node (ref "OBD_HDR") (pin "10") (pinfunction "10_10") (pintype "passive"))
    )
    (net (code "38") (name "JTAG_TCK") (class "Default")
      (node (ref "AVR") (pin "P$12") (pinfunction "PB6_P$12") (pintype "bidirectional"))
      (node (ref "JTAG_HDR") (pin "1") (pinfunction "1_1") (pintype "passive"))
    )
    (net (code "39") (name "JTAG_TDI") (class "Default")
      (node (ref "AVR") (pin "P$11") (pinfunction "PB5_P$11") (pintype "bidirectional"))
      (node (ref "JTAG_HDR") (pin "9") (pinfunction "9_9") (pintype "passive"))
    )
    (net (code "40") (name "JTAG_TDO") (class "Default")
      (node (ref "AVR") (pin "P$13") (pinfunction "PB7_P$13") (pintype "bidirectional"))
      (node (ref "JTAG_HDR") (pin "3") (pinfunction "3_3") (pintype "passive"))
    )
    (net (code "41") (name "JTAG_TMS") (class "Default")
      (node (ref "AVR") (pin "P$10") (pinfunction "PB4_P$10") (pintype "bidirectional"))
      (node (ref "JTAG_HDR") (pin "5") (pinfunction "5_5") (pintype "passive"))
    )
    (net (code "42") (name "LCD_A0") (class "Default")
      (node (ref "AVR") (pin "P$18") (pinfunction "PC2_P$18") (pintype "bidirectional"))
      (node (ref "LCD_HDR") (pin "3") (pinfunction "3_3") (pintype "passive"))
    )
    (net (code "43") (name "LCD_BL_B-") (class "Default")
      (node (ref "LCD_HDR") (pin "11") (pinfunction "11_11") (pintype "passive"))
      (node (ref "R_BLU_LED") (pin "2") (pinfunction "2_2") (pintype "passive"))
    )
    (net (code "44") (name "LCD_BL_G-") (class "Default")
      (node (ref "LCD_HDR") (pin "10") (pinfunction "10_10") (pintype "passive"))
      (node (ref "R_GRN_LED") (pin "2") (pinfunction "2_2") (pintype "passive"))
    )
    (net (code "45") (name "LCD_BL_R-") (class "Default")
      (node (ref "LCD_HDR") (pin "8") (pinfunction "8_8") (pintype "passive"))
      (node (ref "R_RED_LED") (pin "2") (pinfunction "2_2") (pintype "passive"))
    )
    (net (code "46") (name "LCD_RESET") (class "Default")
      (node (ref "AVR") (pin "P$16") (pinfunction "PC0_P$16") (pintype "bidirectional"))
      (node (ref "LCD_HDR") (pin "2") (pinfunction "2_2") (pintype "passive"))
      (node (ref "R_LCD_RESET") (pin "1") (pinfunction "1_1") (pintype "passive"))
    )
    (net (code "47") (name "LCD_SCLK") (class "Default")
      (node (ref "AVR") (pin "P$17") (pinfunction "PC1_P$17") (pintype "bidirectional"))
      (node (ref "LCD_HDR") (pin "4") (pinfunction "4_4") (pintype "passive"))
    )
    (net (code "48") (name "LCD_SID") (class "Default")
      (node (ref "AVR") (pin "P$19") (pinfunction "PC3_P$19") (pintype "bidirectional"))
      (node (ref "LCD_HDR") (pin "5") (pinfunction "5_5") (pintype "passive"))
    )
    (net (code "49") (name "Net-(AVR-AVCC)") (class "Default")
      (node (ref "AVR") (pin "P$61") (pinfunction "AVCC_P$61") (pintype "power_in"))
      (node (ref "BEAD_AVR_ANALOG") (pin "1") (pinfunction "1_1") (pintype "passive"))
      (node (ref "C_AVR_ANALOG") (pin "1") (pinfunction "1_1") (pintype "passive"))
      (node (ref "C_AVR_ANALOG_LOCAL") (pin "+") (pinfunction "+_+") (pintype "passive"))
    )
    (net (code "50") (name "Net-(AVR-PDI)") (class "Default")
      (node (ref "AVR") (pin "P$56") (pinfunction "PDI_P$56") (pintype "bidirectional"))
      (node (ref "PDI_HDR") (pin "1") (pinfunction "1_1") (pintype "passive"))
    )
    (net (code "51") (name "Net-(AVR-PE0)") (class "Default")
      (node (ref "AVR") (pin "P$36") (pinfunction "PE0_P$36") (pintype "bidirectional"))
      (node (ref "NMOS_BLU") (pin "3") (pinfunction "G_3") (pintype "passive"))
      (node (ref "R_BLU_PD") (pin "2") (pinfunction "2_2") (pintype "passive"))
    )
    (net (code "52") (name "Net-(AVR-PE1)") (class "Default")
      (node (ref "AVR") (pin "P$37") (pinfunction "PE1_P$37") (pintype "bidirectional"))
      (node (ref "NMOS_GRN") (pin "3") (pinfunction "G_3") (pintype "passive"))
      (node (ref "R_GRN_PD") (pin "2") (pinfunction "2_2") (pintype "passive"))
    )
    (net (code "53") (name "Net-(AVR-PE2)") (class "Default")
      (node (ref "AVR") (pin "P$38") (pinfunction "PE2_P$38") (pintype "bidirectional"))
      (node (ref "NMOS_RED") (pin "3") (pinfunction "G_3") (pintype "passive"))
      (node (ref "R_RED_PD") (pin "2") (pinfunction "2_2") (pintype "passive"))
    )
    (net (code "54") (name "Net-(AVR-PR0)") (class "Default")
      (node (ref "AVR") (pin "P$58") (pinfunction "PR0_P$58") (pintype "bidirectional"))
      (node (ref "AVR_XTAL") (pin "1") (pinfunction "1_1") (pintype "passive"))
      (node (ref "C_AVR_XTAL1") (pin "1") (pinfunction "1_1") (pintype "passive"))
    )
    (net (code "55") (name "Net-(AVR-PR1)") (class "Default")
      (node (ref "AVR") (pin "P$59") (pinfunction "PR1_P$59") (pintype "bidirectional"))
      (node (ref "AVR_XTAL") (pin "2") (pinfunction "2_2") (pintype "passive"))
      (node (ref "C_AVR_XTAL2") (pin "1") (pinfunction "1_1") (pintype "passive"))
    )
    (net (code "56") (name "Net-(AVR-VCC-PadP$15)") (class "Default")
      (node (ref "AVR") (pin "P$15") (pinfunction "VCC_P$15") (pintype "power_in"))
      (node (ref "AVR") (pin "P$25") (pinfunction "VCC_P$25") (pintype "power_in"))
      (node (ref "AVR") (pin "P$35") (pinfunction "VCC_P$35") (pintype "power_in"))
      (node (ref "AVR") (pin "P$45") (pinfunction "VCC_P$45") (pintype "power_in"))
      (node (ref "AVR") (pin "P$53") (pinfunction "VCC_P$53") (pintype "power_in"))
      (node (ref "BEAD_AVR_ANALOG") (pin "2") (pinfunction "2_2") (pintype "passive"))
      (node (ref "C1") (pin "1") (pinfunction "1_1") (pintype "passive"))
      (node (ref "C2") (pin "1") (pinfunction "1_1") (pintype "passive"))
      (node (ref "C3") (pin "1") (pinfunction "1_1") (pintype "passive"))
      (node (ref "C4") (pin "1") (pinfunction "1_1") (pintype "passive"))
      (node (ref "C5") (pin "1") (pinfunction "1_1") (pintype "passive"))
      (node (ref "C_AVR_PWR") (pin "+") (pinfunction "+_+") (pintype "passive"))
      (node (ref "L_AVR_PWR") (pin "1") (pinfunction "1_1") (pintype "passive"))
    )
    (net (code "57") (name "Net-(CAN_CTRLR-OSC1)") (class "Default")
      (node (ref "CAN_CTRLR") (pin "P$9") (pinfunction "OSC1_P$9") (pintype "bidirectional"))
      (node (ref "CAN_XTAL") (pin "2") (pinfunction "2_2") (pintype "passive"))
      (node (ref "C_CAN_XTAL1") (pin "1") (pinfunction "1_1") (pintype "passive"))
    )
    (net (code "58") (name "Net-(CAN_CTRLR-OSC2)") (class "Default")
      (node (ref "CAN_CTRLR") (pin "P$8") (pinfunction "OSC2_P$8") (pintype "bidirectional"))
      (node (ref "CAN_XTAL") (pin "1") (pinfunction "1_1") (pintype "passive"))
      (node (ref "C_CAN_XTAL2") (pin "1") (pinfunction "1_1") (pintype "passive"))
    )
    (net (code "59") (name "Net-(CAN_CTRLR-{slash}RESET)") (class "Default")
      (node (ref "CAN_CTRLR") (pin "P$19") (pinfunction "/RESET_P$19") (pintype "bidirectional"))
      (node (ref "R_CAN_RST2") (pin "2") (pinfunction "2_2") (pintype "passive"))
    )
    (net (code "60") (name "Net-(C_CAN_RST-Pad1)") (class "Default")
      (node (ref "C_CAN_RST") (pin "1") (pinfunction "1_1") (pintype "passive"))
      (node (ref "R_CAN_RST1") (pin "1") (pinfunction "1_1") (pintype "passive"))
      (node (ref "R_CAN_RST2") (pin "1") (pinfunction "1_1") (pintype "passive"))
    )
    (net (code "61") (name "Net-(FTDI-3V3OUT)") (class "Default")
      (node (ref "C_FTDI_FLOAT") (pin "1") (pinfunction "1_1") (pintype "passive"))
      (node (ref "FTDI") (pin "P$13") (pinfunction "3V3OUT_P$13") (pintype "power_in"))
      (node (ref "FTDI") (pin "P$14") (pinfunction "RESET#_P$14") (pintype "bidirectional"))
      (node (ref "FTDI") (pin "P$3") (pinfunction "VCCIO_P$3") (pintype "power_in"))
    )
    (net (code "62") (name "Net-(FTDI-CBUS1)") (class "Default")
      (node (ref "FTDI") (pin "P$17") (pinfunction "CBUS1_P$17") (pintype "bidirectional"))
      (node (ref "R_FTDI_RX_LED") (pin "2") (pinfunction "2_2") (pintype "passive"))
    )
    (net (code "63") (name "Net-(FTDI-CBUS2)") (class "Default")
      (node (ref "FTDI") (pin "P$10") (pinfunction "CBUS2_P$10") (pintype "bidirectional"))
      (node (ref "R_FTDI_TX_LED") (pin "2") (pinfunction "2_2") (pintype "passive"))
    )
    (net (code "64") (name "Net-(FTDI-USBDM)") (class "Default")
      (node (ref "FTDI") (pin "P$12") (pinfunction "USBDM_P$12") (pintype "bidirectional"))
      (node (ref "R_USB-") (pin "1") (pinfunction "1_1") (pintype "passive"))
    )
    (net (code "65") (name "Net-(FTDI-USBDP)") (class "Default")
      (node (ref "FTDI") (pin "P$11") (pinfunction "USBDP_P$11") (pintype "bidirectional"))
      (node (ref "R_USB+") (pin "1") (pinfunction "1_1") (pintype "passive"))
    )
    (net (code "66") (name "Net-(FTDI_RX_LED-PadC)") (class "Default")
      (node (ref "FTDI_RX_LED") (pin "C") (pinfunction "C_C") (pintype "passive"))
      (node (ref "R_FTDI_RX_LED") (pin "1") (pinfunction "1_1") (pintype "passive"))
    )
    (net (code "67") (name "Net-(FTDI_TX_LED-PadC)") (class "Default")
      (node (ref "FTDI_TX_LED") (pin "C") (pinfunction "C_C") (pintype "passive"))
      (node (ref "R_FTDI_TX_LED") (pin "1") (pinfunction "1_1") (pintype "passive"))
    )
    (net (code "68") (name "Net-(GPS-VCC)") (class "Default")
      (node (ref "BEAD_GPS") (pin "2") (pinfunction "2_2") (pintype "passive"))
      (node (ref "C_GPS_PWR1") (pin "1") (pinfunction "1_1") (pintype "passive"))
      (node (ref "C_GPS_PWR2") (pin "+") (pinfunction "+_+") (pintype "passive"))
      (node (ref "GPS") (pin "P$1") (pinfunction "VCC_P$1") (pintype "power_in"))
    )
    (net (code "69") (name "Net-(MINIUSB-D+)") (class "Default")
      (node (ref "C_USB+") (pin "1") (pinfunction "1_1") (pintype "passive"))
      (node (ref "MINIUSB") (pin "P$3") (pinfunction "D+_P$3") (pintype "bidirectional"))
      (node (ref "R_USB+") (pin "2") (pinfunction "2_2") (pintype "passive"))
    )
    (net (code "70") (name "Net-(MINIUSB-D-)") (class "Default")
      (node (ref "C_USB-") (pin "1") (pinfunction "1_1") (pintype "passive"))
      (node (ref "MINIUSB") (pin "P$2") (pinfunction "D-_P$2") (pintype "bidirectional"))
      (node (ref "R_USB-") (pin "2") (pinfunction "2_2") (pintype "passive"))
    )
    (net (code "71") (name "Net-(MINIUSB-VBUS)") (class "Default")
      (node (ref "MINIUSB") (pin "P$1") (pinfunction "VBUS_P$1") (pintype "power_in"))
      (node (ref "R_VBUS_HIGH") (pin "2") (pinfunction "2_2") (pintype "passive"))
    )
    (net (code "72") (name "Net-(NMOS_BLU-S)") (class "Default")
      (node (ref "NMOS_BLU") (pin "2") (pinfunction "S_2") (pintype "passive"))
      (node (ref "R_BLU_LED") (pin "1") (pinfunction "1_1") (pintype "passive"))
    )
    (net (code "73") (name "Net-(NMOS_GRN-S)") (class "Default")
      (node (ref "NMOS_GRN") (pin "2") (pinfunction "S_2") (pintype "passive"))
      (node (ref "R_GRN_LED") (pin "1") (pinfunction "1_1") (pintype "passive"))
    )
    (net (code "74") (name "Net-(NMOS_RED-S)") (class "Default")
      (node (ref "NMOS_RED") (pin "2") (pinfunction "S_2") (pintype "passive"))
      (node (ref "R_RED_LED") (pin "1") (pinfunction "1_1") (pintype "passive"))
    )
    (net (code "75") (name "Net-(PWR_LED-PadC)") (class "Default")
      (node (ref "PWR_LED") (pin "C") (pinfunction "C_C") (pintype "passive"))
      (node (ref "R_PWR_LED") (pin "2") (pinfunction "2_2") (pintype "passive"))
    )
    (net (code "76") (name "Net-(RTC-X1)") (class "Default")
      (node (ref "C_RTC_XTAL2") (pin "1") (pinfunction "1_1") (pintype "passive"))
      (node (ref "RTC") (pin "P$1") (pinfunction "X1_P$1") (pintype "bidirectional"))
      (node (ref "RTC_XTAL") (pin "2") (pinfunction "2_2") (pintype "passive"))
    )
    (net (code "77") (name "Net-(RTC-X2)") (class "Default")
      (node (ref "C_RTC_XTAL1") (pin "1") (pinfunction "1_1") (pintype "passive"))
      (node (ref "RTC") (pin "P$2") (pinfunction "X2_P$2") (pintype "bidirectional"))
      (node (ref "RTC_XTAL") (pin "1") (pinfunction "1_1") (pintype "passive"))
    )
    (net (code "78") (name "RESET") (class "Default")
      (node (ref "AVR") (pin "P$57") (pinfunction "RESET_P$57") (pintype "bidirectional"))
      (node (ref "JTAG_HDR") (pin "6") (pinfunction "6_6") (pintype "passive"))
      (node (ref "PDI_HDR") (pin "5") (pinfunction "5_5") (pintype "passive"))
      (node (ref "R_RESET_PU") (pin "1") (pinfunction "1_1") (pintype "passive"))
      (node (ref "SW_RESET") (pin "2") (pinfunction "2_2") (pintype "passive"))
    )
    (net (code "79") (name "RTC_INT") (class "Default")
      (node (ref "AVR") (pin "P$47") (pinfunction "PF1_P$47") (pintype "bidirectional"))
      (node (ref "RTC") (pin "P$9") (pinfunction "SQW/INT_P$9") (pintype "output"))
      (node (ref "R_RTC_INT") (pin "1") (pinfunction "1_1") (pintype "passive"))
    )
    (net (code "80") (name "RTC_MISO") (class "Default")
      (node (ref "AVR") (pin "P$22") (pinfunction "PC6_P$22") (pintype "bidirectional"))
      (node (ref "RTC") (pin "P$7") (pinfunction "DOUT_P$7") (pintype "output"))
    )
    (net (code "81") (name "RTC_MOSI") (class "Default")
      (node (ref "AVR") (pin "P$21") (pinfunction "PC5_P$21") (pintype "bidirectional"))
      (node (ref "RTC") (pin "P$6") (pinfunction "DIN_P$6") (pintype "input"))
    )
    (net (code "82") (name "RTC_SCK") (class "Default")
      (node (ref "AVR") (pin "P$23") (pinfunction "PC7_P$23") (pintype "bidirectional"))
      (node (ref "RTC") (pin "P$8") (pinfunction "SCLK_P$8") (pintype "input"))
    )
    (net (code "83") (name "RTC_SS") (class "Default")
      (node (ref "AVR") (pin "P$20") (pinfunction "PC4_P$20") (pintype "bidirectional"))
      (node (ref "RTC") (pin "P$4") (pinfunction "/CS_P$4") (pintype "input"))
      (node (ref "R_RTC_SS") (pin "2") (pinfunction "2_2") (pintype "passive"))
    )
    (net (code "84") (name "SD_DAT1") (class "Default")
      (node (ref "AVR") (pin "P$6") (pinfunction "PB0_P$6") (pintype "bidirectional"))
      (node (ref "MICROSD") (pin "P$8") (pinfunction "NC/DAT1_P$8") (pintype "bidirectional"))
    )
    (net (code "85") (name "SD_DAT2") (class "Default")
      (node (ref "AVR") (pin "P$7") (pinfunction "PB1_P$7") (pintype "bidirectional"))
      (node (ref "MICROSD") (pin "P$1") (pinfunction "NC/DAT2_P$1") (pintype "bidirectional"))
    )
    (net (code "86") (name "SD_DETECT") (class "Default")
      (node (ref "AVR") (pin "P$39") (pinfunction "PE3_P$39") (pintype "bidirectional"))
      (node (ref "MICROSD") (pin "P$9") (pinfunction "DETECT_P$9") (pintype "bidirectional"))
      (node (ref "R_SD_DETECT") (pin "1") (pinfunction "1_1") (pintype "passive"))
    )
    (net (code "87") (name "SD_MISO") (class "Default")
      (node (ref "AVR") (pin "P$42") (pinfunction "PE6_P$42") (pintype "bidirectional"))
      (node (ref "MICROSD") (pin "P$7") (pinfunction "DO/DAT0_P$7") (pintype "output"))
    )
    (net (code "88") (name "SD_MOSI") (class "Default")
      (node (ref "AVR") (pin "P$41") (pinfunction "PE5_P$41") (pintype "bidirectional"))
      (node (ref "MICROSD") (pin "P$3") (pinfunction "DI/CMD_P$3") (pintype "input"))
    )
    (net (code "89") (name "SD_SCK") (class "Default")
      (node (ref "AVR") (pin "P$43") (pinfunction "PE7_P$43") (pintype "bidirectional"))
      (node (ref "MICROSD") (pin "P$5") (pinfunction "SCLK/CLK_P$5") (pintype "input"))
    )
    (net (code "90") (name "SD_SS") (class "Default")
      (node (ref "AVR") (pin "P$40") (pinfunction "PE4_P$40") (pintype "bidirectional"))
      (node (ref "MICROSD") (pin "P$2") (pinfunction "CS/DAT3_P$2") (pintype "input"))
      (node (ref "R_SD_SS") (pin "2") (pinfunction "2_2") (pintype "passive"))
    )
    (net (code "91") (name "VBACKUP") (class "Default")
      (node (ref "C_GPS_BATT") (pin "+") (pinfunction "+_+") (pintype "passive"))
      (node (ref "GPS") (pin "P$4") (pinfunction "VBACKUP_P$4") (pintype "power_in"))
      (node (ref "RTC") (pin "P$3") (pinfunction "VBACKUP_P$3") (pintype "power_in"))
      (node (ref "RTC_BATT") (pin "P$1") (pinfunction "+_P$1") (pintype "power_in"))
    )
    (net (code "92") (name "VBUS_SENSE") (class "Default")
      (node (ref "FTDI") (pin "P$18") (pinfunction "CBUS0_P$18") (pintype "bidirectional"))
      (node (ref "R_VBUS_HIGH") (pin "1") (pinfunction "1_1") (pintype "passive"))
      (node (ref "R_VBUS_LOW") (pin "2") (pinfunction "2_2") (pintype "passive"))
    )
    (net (code "93") (name "unconnected-(AVR-PB3-PadP$9)") (class "Default")
      (node (ref "AVR") (pin "P$9") (pinfunction "PB3_P$9") (pintype "bidirectional"))
    )
    (net (code "94") (name "unconnected-(AVR-PF0-PadP$46)") (class "Default")
      (node (ref "AVR") (pin "P$46") (pinfunction "PF0_P$46") (pintype "bidirectional"))
    )
    (net (code "95") (name "unconnected-(AVR-PF6-PadP$54)") (class "Default")
      (node (ref "AVR") (pin "P$54") (pinfunction "PF6_P$54") (pintype "bidirectional"))
    )
    (net (code "96") (name "unconnected-(AVR-PF7-PadP$55)") (class "Default")
      (node (ref "AVR") (pin "P$55") (pinfunction "PF7_P$55") (pintype "bidirectional"))
    )
    (net (code "97") (name "unconnected-(BTN_HDR-Pad9)") (class "Default")
      (node (ref "BTN_HDR") (pin "9") (pinfunction "9_9") (pintype "passive"))
    )
    (net (code "98") (name "unconnected-(CAN_CTRLR-CLKOUT{slash}SOF-PadP$3)") (class "Default")
      (node (ref "CAN_CTRLR") (pin "P$3") (pinfunction "CLKOUT/SOF_P$3") (pintype "bidirectional"))
    )
    (net (code "99") (name "unconnected-(CAN_CTRLR-{slash}RX0BF-PadP$12)") (class "Default")
      (node (ref "CAN_CTRLR") (pin "P$12") (pinfunction "/RX0BF_P$12") (pintype "bidirectional"))
    )
    (net (code "100") (name "unconnected-(CAN_CTRLR-{slash}RX1BF-PadP$11)") (class "Default")
      (node (ref "CAN_CTRLR") (pin "P$11") (pinfunction "/RX1BF_P$11") (pintype "bidirectional"))
    )
    (net (code "101") (name "unconnected-(CAN_CTRLR-{slash}TX0RTS-PadP$4)") (class "Default")
      (node (ref "CAN_CTRLR") (pin "P$4") (pinfunction "/TX0RTS_P$4") (pintype "bidirectional"))
    )
    (net (code "102") (name "unconnected-(CAN_CTRLR-{slash}TX1RTS-PadP$5)") (class "Default")
      (node (ref "CAN_CTRLR") (pin "P$5") (pinfunction "/TX1RTS_P$5") (pintype "bidirectional"))
    )
    (net (code "103") (name "unconnected-(CAN_CTRLR-{slash}TX2RTS-PadP$7)") (class "Default")
      (node (ref "CAN_CTRLR") (pin "P$7") (pinfunction "/TX2RTS_P$7") (pintype "bidirectional"))
    )
    (net (code "104") (name "unconnected-(FTDI-CBUS3-PadP$19)") (class "Default")
      (node (ref "FTDI") (pin "P$19") (pinfunction "CBUS3_P$19") (pintype "bidirectional"))
    )
    (net (code "105") (name "unconnected-(GPS-3D_FIX-PadP$5)") (class "Default")
      (node (ref "GPS") (pin "P$5") (pinfunction "3D_FIX_P$5") (pintype "bidirectional"))
    )
    (net (code "106") (name "unconnected-(GPS-EX_ANT-PadP$11)") (class "Default")
      (node (ref "GPS") (pin "P$11") (pinfunction "EX_ANT_P$11") (pintype "bidirectional"))
    )
    (net (code "107") (name "unconnected-(GPS-NRESET-PadP$2)") (class "Default")
      (node (ref "GPS") (pin "P$2") (pinfunction "NRESET_P$2") (pintype "bidirectional"))
    )
    (net (code "108") (name "unconnected-(GPS-RTCM-PadP$14)") (class "Default")
      (node (ref "GPS") (pin "P$14") (pinfunction "RTCM_P$14") (pintype "bidirectional"))
    )
    (net (code "109") (name "unconnected-(JTAG_HDR-Pad7)") (class "Default")
      (node (ref "JTAG_HDR") (pin "7") (pinfunction "7_7") (pintype "passive"))
    )
    (net (code "110") (name "unconnected-(JTAG_HDR-Pad8)") (class "Default")
      (node (ref "JTAG_HDR") (pin "8") (pinfunction "8_8") (pintype "passive"))
    )
    (net (code "111") (name "unconnected-(LCD_HDR-Pad12)") (class "Default")
      (node (ref "LCD_HDR") (pin "12") (pinfunction "12_12") (pintype "passive"))
    )
    (net (code "112") (name "unconnected-(MINIUSB-ID-PadP$4)") (class "Default")
      (node (ref "MINIUSB") (pin "P$4") (pinfunction "ID_P$4") (pintype "bidirectional"))
    )
    (net (code "113") (name "unconnected-(OBD_HDR-Pad2)") (class "Default")
      (node (ref "OBD_HDR") (pin "2") (pinfunction "2_2") (pintype "passive"))
    )
    (net (code "114") (name "unconnected-(OBD_HDR-Pad4)") (class "Default")
      (node (ref "OBD_HDR") (pin "4") (pinfunction "4_4") (pintype "passive"))
    )
    (net (code "115") (name "unconnected-(PDI_HDR-Pad3)") (class "Default")
      (node (ref "PDI_HDR") (pin "3") (pinfunction "3_3") (pintype "passive"))
    )
    (net (code "116") (name "unconnected-(PDI_HDR-Pad4)") (class "Default")
      (node (ref "PDI_HDR") (pin "4") (pinfunction "4_4") (pintype "passive"))
    )
    (net (code "117") (name "unconnected-(SW_RESET-Pad1)") (class "Default")
      (node (ref "SW_RESET") (pin "1") (pinfunction "1_1") (pintype "passive"))
    )
    (net (code "118") (name "unconnected-(SW_RESET-Pad3)") (class "Default")
      (node (ref "SW_RESET") (pin "3") (pinfunction "3_3") (pintype "passive"))
    )
  )
)
